# right_revision3_0.net
KiCad netlist of a schematic drawn in EAGLE
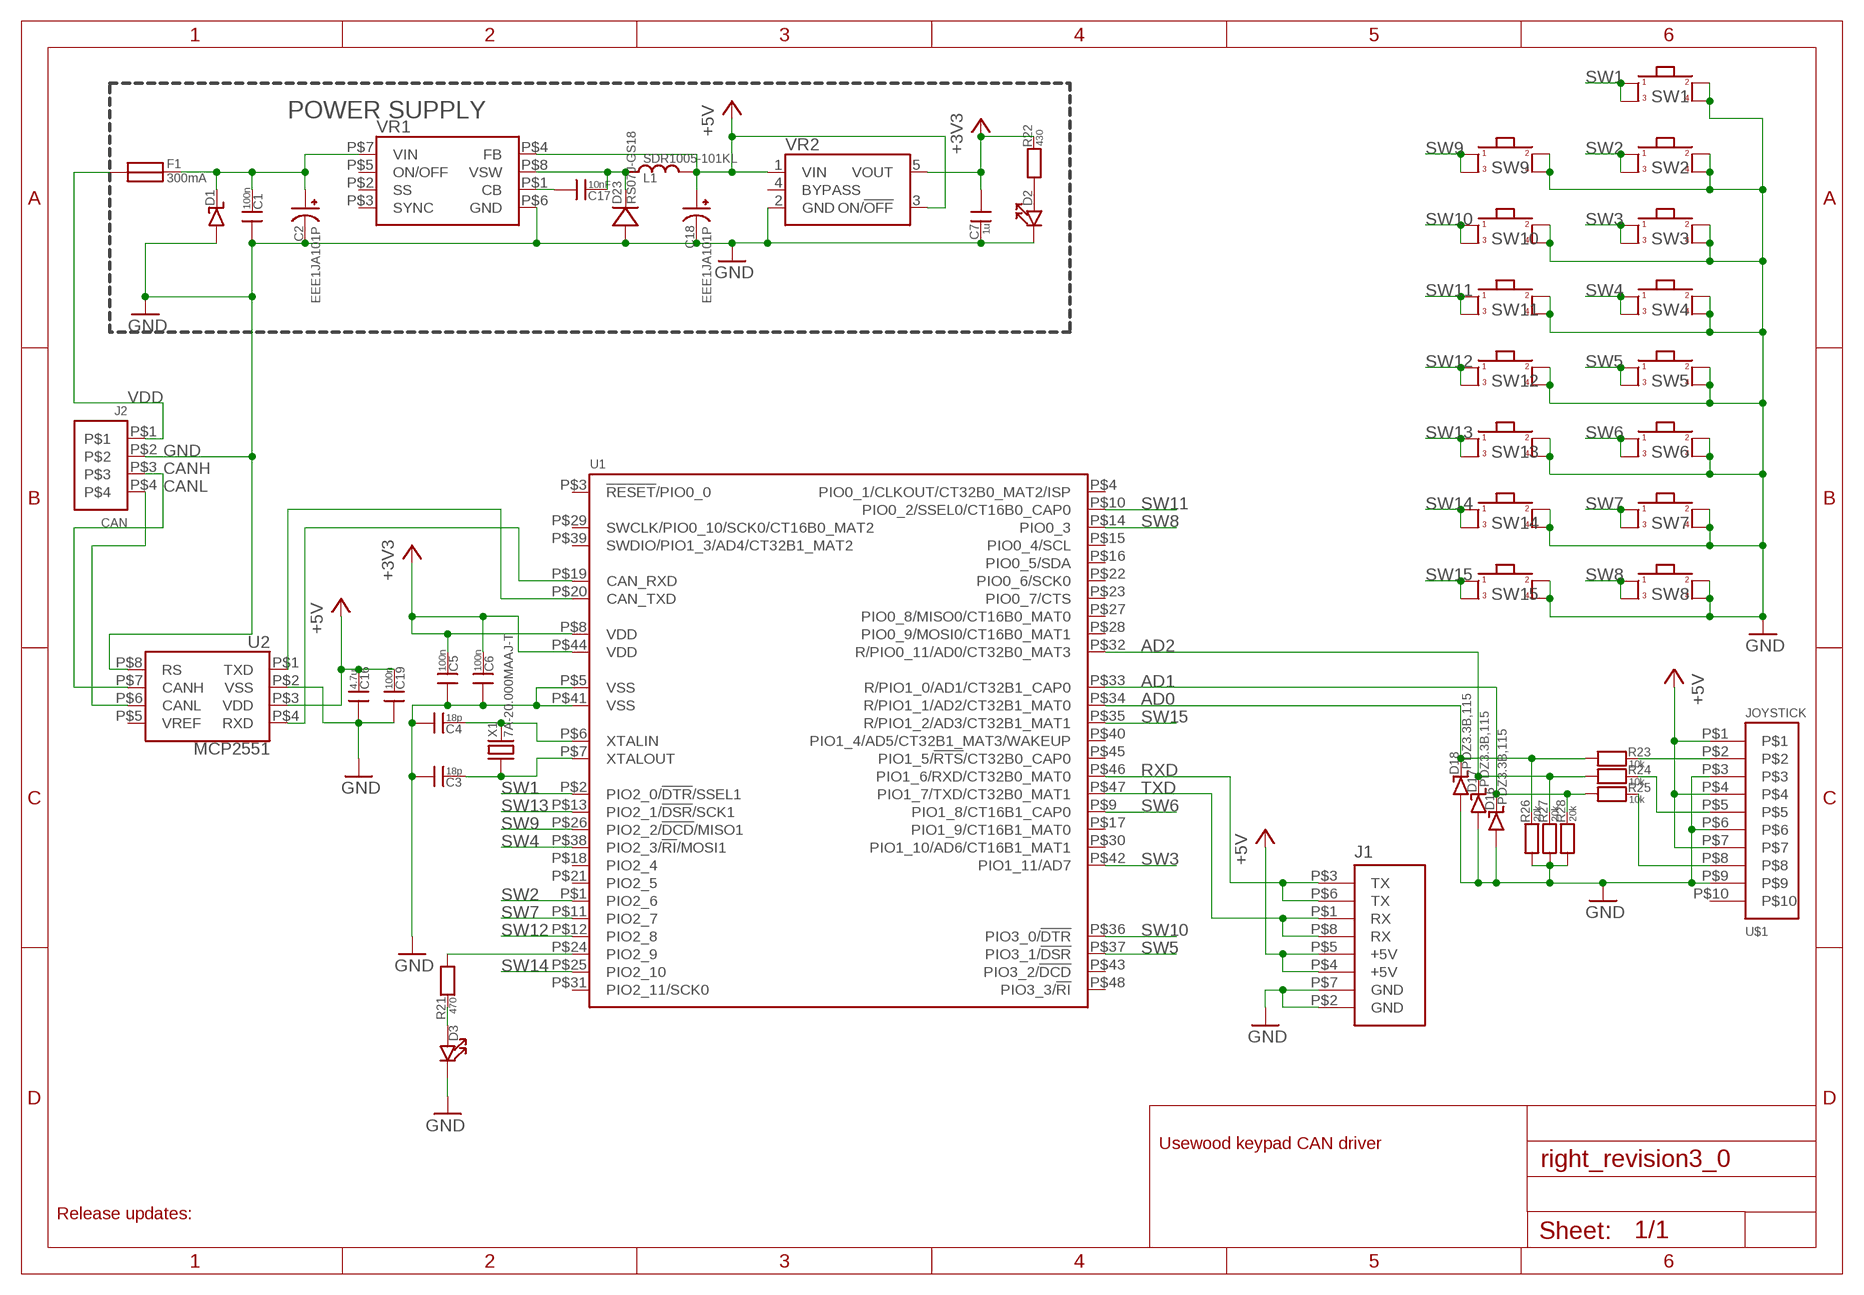
[diagram p0: schematic, sheet 1]

(export (version "E")
  (design (tool "Eeschema 10.0.6"))
  (components
    (comp (ref "C1")
      (value "100n")
      (footprint "eagle-import:0603_SILKSCREEN")
      (libsource (lib "eagle-import") (part "CAP_0603"))
    )
    (comp (ref "C2")
      (value "EEE1JA101P")
      (footprint "eagle-import:CAP_POL_SMD_10X10X10MM")
      (libsource (lib "eagle-import") (part "CAP_POLSMD_10X10X10MM"))
    )
    (comp (ref "C3")
      (value "18p")
      (footprint "eagle-import:0603_SILKSCREEN")
      (libsource (lib "eagle-import") (part "CAP_0603"))
    )
    (comp (ref "C4")
      (value "18p")
      (footprint "eagle-import:0603_SILKSCREEN")
      (libsource (lib "eagle-import") (part "CAP_0603"))
    )
    (comp (ref "C5")
      (value "100n")
      (footprint "eagle-import:0603_SILKSCREEN")
      (libsource (lib "eagle-import") (part "CAP_0603"))
    )
    (comp (ref "C6")
      (value "100n")
      (footprint "eagle-import:0603_SILKSCREEN")
      (libsource (lib "eagle-import") (part "CAP_0603"))
    )
    (comp (ref "C7")
      (value "1u")
      (footprint "eagle-import:0603_SILKSCREEN")
      (libsource (lib "eagle-import") (part "CAP_0603"))
    )
    (comp (ref "C16")
      (value "4.7u")
      (footprint "eagle-import:0603_SILKSCREEN")
      (libsource (lib "eagle-import") (part "CAP_0603"))
    )
    (comp (ref "C17")
      (value "10nF")
      (footprint "eagle-import:0603_SILKSCREEN")
      (libsource (lib "eagle-import") (part "CAP_0603"))
    )
    (comp (ref "C18")
      (value "EEE1JA101P")
      (footprint "eagle-import:CAP_POL_SMD_10X10X10MM")
      (libsource (lib "eagle-import") (part "CAP_POLSMD_10X10X10MM"))
    )
    (comp (ref "C19")
      (value "100n")
      (footprint "eagle-import:0603_SILKSCREEN")
      (libsource (lib "eagle-import") (part "CAP_0603"))
    )
    (comp (ref "D1")
      (value "DIODE_TVS_SMBJ33A-TRDO-214AA")
      (footprint "eagle-import:DO-214AA")
      (libsource (lib "eagle-import") (part "DIODE_TVS_SMBJ33A-TRDO-214AA"))
    )
    (comp (ref "D2")
      (value "LED_0603")
      (footprint "eagle-import:0603_SILKSCREEN")
      (libsource (lib "eagle-import") (part "LED_0603"))
    )
    (comp (ref "D3")
      (value "LED_0603")
      (footprint "eagle-import:0603_SILKSCREEN")
      (libsource (lib "eagle-import") (part "LED_0603"))
    )
    (comp (ref "D16")
      (value "PDZ3.3B,115")
      (footprint "eagle-import:SOD123")
      (libsource (lib "eagle-import") (part "DIODE_ZENERSDO123"))
    )
    (comp (ref "D17")
      (value "PDZ3.3B,115")
      (footprint "eagle-import:SOD123")
      (libsource (lib "eagle-import") (part "DIODE_ZENERSDO123"))
    )
    (comp (ref "D18")
      (value "PDZ3.3B,115")
      (footprint "eagle-import:SOD123")
      (libsource (lib "eagle-import") (part "DIODE_ZENERSDO123"))
    )
    (comp (ref "D23")
      (value "RS07J-GS18")
      (footprint "eagle-import:DO219AB")
      (libsource (lib "eagle-import") (part "DIODEDO219AB"))
    )
    (comp (ref "F1")
      (value "300mA")
      (footprint "eagle-import:FUSE_100MA")
      (libsource (lib "eagle-import") (part "FUSE_MC36204_100MA"))
    )
    (comp (ref "J1")
      (value "HEADER_USART_2_SMD")
      (footprint "eagle-import:HEADER_4_2_SMD")
      (libsource (lib "eagle-import") (part "HEADER_USART_2_SMD"))
    )
    (comp (ref "J2")
      (value "CAN")
      (footprint "eagle-import:MOLEX_MICRO_FIT_4WAY_SMD")
      (libsource (lib "eagle-import") (part "MOLEX_MICRO-FIT_4WAY_SMD"))
    )
    (comp (ref "L1")
      (value "SDR1005-101KL")
      (footprint "eagle-import:INDUCTOR_BOURNS_10X13X5MM")
      (libsource (lib "eagle-import") (part "INDUCTORBOURNS_10X13X5MM"))
    )
    (comp (ref "R21")
      (value "470")
      (footprint "eagle-import:0603_SILKSCREEN")
      (libsource (lib "eagle-import") (part "RES_0603"))
    )
    (comp (ref "R22")
      (value "430")
      (footprint "eagle-import:0603_SILKSCREEN")
      (libsource (lib "eagle-import") (part "RES_0603"))
    )
    (comp (ref "R23")
      (value "10k")
      (footprint "eagle-import:0603_SILKSCREEN")
      (libsource (lib "eagle-import") (part "RES_0603"))
    )
    (comp (ref "R24")
      (value "10k")
      (footprint "eagle-import:0603_SILKSCREEN")
      (libsource (lib "eagle-import") (part "RES_0603"))
    )
    (comp (ref "R25")
      (value "10k")
      (footprint "eagle-import:0603_SILKSCREEN")
      (libsource (lib "eagle-import") (part "RES_0603"))
    )
    (comp (ref "R26")
      (value "20k")
      (footprint "eagle-import:0603_SILKSCREEN")
      (libsource (lib "eagle-import") (part "RES_0603"))
    )
    (comp (ref "R27")
      (value "20k")
      (footprint "eagle-import:0603_SILKSCREEN")
      (libsource (lib "eagle-import") (part "RES_0603"))
    )
    (comp (ref "R28")
      (value "20k")
      (footprint "eagle-import:0603_SILKSCREEN")
      (libsource (lib "eagle-import") (part "RES_0603"))
    )
    (comp (ref "SW1")
      (value "SWITCH_EVQP6L")
      (footprint "eagle-import:SWITCH_EVQ9P6B40")
      (libsource (lib "eagle-import") (part "SWITCH_EVQP6L"))
    )
    (comp (ref "SW2")
      (value "SWITCH_EVQP6L")
      (footprint "eagle-import:SWITCH_EVQ9P6B40")
      (libsource (lib "eagle-import") (part "SWITCH_EVQP6L"))
    )
    (comp (ref "SW3")
      (value "SWITCH_EVQP6L")
      (footprint "eagle-import:SWITCH_EVQ9P6B40")
      (libsource (lib "eagle-import") (part "SWITCH_EVQP6L"))
    )
    (comp (ref "SW4")
      (value "SWITCH_EVQP6L")
      (footprint "eagle-import:SWITCH_EVQ9P6B40")
      (libsource (lib "eagle-import") (part "SWITCH_EVQP6L"))
    )
    (comp (ref "SW5")
      (value "SWITCH_EVQP6L")
      (footprint "eagle-import:SWITCH_EVQ9P6B40")
      (libsource (lib "eagle-import") (part "SWITCH_EVQP6L"))
    )
    (comp (ref "SW6")
      (value "SWITCH_EVQP6L")
      (footprint "eagle-import:SWITCH_EVQ9P6B40")
      (libsource (lib "eagle-import") (part "SWITCH_EVQP6L"))
    )
    (comp (ref "SW7")
      (value "SWITCH_EVQP6L")
      (footprint "eagle-import:SWITCH_EVQ9P6B40")
      (libsource (lib "eagle-import") (part "SWITCH_EVQP6L"))
    )
    (comp (ref "SW8")
      (value "SWITCH_EVQP6L")
      (footprint "eagle-import:SWITCH_EVQ9P6B40")
      (libsource (lib "eagle-import") (part "SWITCH_EVQP6L"))
    )
    (comp (ref "SW9")
      (value "SWITCH_EVQP6L")
      (footprint "eagle-import:SWITCH_EVQ9P6B40")
      (libsource (lib "eagle-import") (part "SWITCH_EVQP6L"))
    )
    (comp (ref "SW10")
      (value "SWITCH_EVQP6L")
      (footprint "eagle-import:SWITCH_EVQ9P6B40")
      (libsource (lib "eagle-import") (part "SWITCH_EVQP6L"))
    )
    (comp (ref "SW11")
      (value "SWITCH_EVQP6L")
      (footprint "eagle-import:SWITCH_EVQ9P6B40")
      (libsource (lib "eagle-import") (part "SWITCH_EVQP6L"))
    )
    (comp (ref "SW12")
      (value "SWITCH_EVQP6L")
      (footprint "eagle-import:SWITCH_EVQ9P6B40")
      (libsource (lib "eagle-import") (part "SWITCH_EVQP6L"))
    )
    (comp (ref "SW13")
      (value "SWITCH_EVQP6L")
      (footprint "eagle-import:SWITCH_EVQ9P6B40")
      (libsource (lib "eagle-import") (part "SWITCH_EVQP6L"))
    )
    (comp (ref "SW14")
      (value "SWITCH_EVQP6L")
      (footprint "eagle-import:SWITCH_EVQ9P6B40")
      (libsource (lib "eagle-import") (part "SWITCH_EVQP6L"))
    )
    (comp (ref "SW15")
      (value "SWITCH_EVQP6L")
      (footprint "eagle-import:SWITCH_EVQ9P6B40")
      (libsource (lib "eagle-import") (part "SWITCH_EVQP6L"))
    )
    (comp (ref "U$1")
      (value "JOYSTICK")
      (footprint "eagle-import:MOLEX_MICRO_FIT_10WAY_SMD")
      (libsource (lib "eagle-import") (part "MOLEX_MICRO-FIT_10WAY_SMD"))
    )
    (comp (ref "U1")
      (value "LPC11C14_QFP48")
      (footprint "eagle-import:QFP48")
      (libsource (lib "eagle-import") (part "LPC11C14_QFP48"))
    )
    (comp (ref "U2")
      (value "MCP2551")
      (footprint "eagle-import:SOIC8")
      (libsource (lib "eagle-import") (part "MCP2551_SOIC8"))
    )
    (comp (ref "VR1")
      (value "LM2671SOIC8")
      (footprint "eagle-import:SOIC8")
      (libsource (lib "eagle-import") (part "LM2671SOIC8"))
    )
    (comp (ref "VR2")
      (value "REG_LP2985_SOP5")
      (footprint "eagle-import:SOP5")
      (libsource (lib "eagle-import") (part "REG_LP2985_SOP5"))
    )
    (comp (ref "X1")
      (value "7A-20.000MAAJ-T")
      (footprint "eagle-import:XTAL_SMD_5X3.2")
      (libsource (lib "eagle-import") (part "XTAL_7A-12.000MAAJ-T"))
    )
  )
  (nets
    (net (code "1") (name "+3V3") (class "Default")
      (node (ref "C5") (pin "1") (pinfunction "P$2_1") (pintype "bidirectional"))
      (node (ref "C6") (pin "1") (pinfunction "P$2_1") (pintype "bidirectional"))
      (node (ref "C7") (pin "0") (pinfunction "P$1_0") (pintype "bidirectional"))
      (node (ref "R22") (pin "1") (pinfunction "P$2_1") (pintype "bidirectional"))
      (node (ref "U1") (pin "P$44") (pinfunction "VDD_P$44") (pintype "bidirectional"))
      (node (ref "U1") (pin "P$8") (pinfunction "VDD_P$8") (pintype "bidirectional"))
      (node (ref "VR2") (pin "5") (pinfunction "VOUT_5") (pintype "bidirectional"))
    )
    (net (code "2") (name "+5V") (class "Default")
      (node (ref "C16") (pin "1") (pinfunction "P$2_1") (pintype "bidirectional"))
      (node (ref "C18") (pin "+") (pinfunction "+_+") (pintype "bidirectional"))
      (node (ref "C19") (pin "1") (pinfunction "P$2_1") (pintype "bidirectional"))
      (node (ref "J1") (pin "P$4") (pinfunction "+5V_P$4") (pintype "bidirectional"))
      (node (ref "J1") (pin "P$5") (pinfunction "+5V_P$5") (pintype "bidirectional"))
      (node (ref "L1") (pin "P$2") (pinfunction "P$2_P$2") (pintype "bidirectional"))
      (node (ref "U$1") (pin "P$1") (pinfunction "P$1_P$1") (pintype "bidirectional"))
      (node (ref "U$1") (pin "P$4") (pinfunction "P$4_P$4") (pintype "bidirectional"))
      (node (ref "U$1") (pin "P$7") (pinfunction "P$7_P$7") (pintype "bidirectional"))
      (node (ref "U2") (pin "P$3") (pinfunction "VDD_P$3") (pintype "bidirectional"))
      (node (ref "VR1") (pin "P$4") (pinfunction "FB_P$4") (pintype "bidirectional"))
      (node (ref "VR2") (pin "1") (pinfunction "VIN_1") (pintype "bidirectional"))
      (node (ref "VR2") (pin "3") (pinfunction "ON/~{OFF}_3") (pintype "bidirectional"))
    )
    (net (code "3") (name "/AD0") (class "Default")
      (node (ref "D18") (pin "P$2") (pinfunction "N_P$2") (pintype "bidirectional"))
      (node (ref "R23") (pin "0") (pinfunction "P$1_0") (pintype "bidirectional"))
      (node (ref "R26") (pin "1") (pinfunction "P$2_1") (pintype "bidirectional"))
      (node (ref "U1") (pin "P$34") (pinfunction "R/PIO1_1/AD2/CT32B1_MAT0_P$34") (pintype "bidirectional"))
    )
    (net (code "4") (name "/AD1") (class "Default")
      (node (ref "D16") (pin "P$2") (pinfunction "N_P$2") (pintype "bidirectional"))
      (node (ref "R25") (pin "0") (pinfunction "P$1_0") (pintype "bidirectional"))
      (node (ref "R28") (pin "1") (pinfunction "P$2_1") (pintype "bidirectional"))
      (node (ref "U1") (pin "P$33") (pinfunction "R/PIO1_0/AD1/CT32B1_CAP0_P$33") (pintype "bidirectional"))
    )
    (net (code "5") (name "/AD2") (class "Default")
      (node (ref "D17") (pin "P$2") (pinfunction "N_P$2") (pintype "bidirectional"))
      (node (ref "R24") (pin "0") (pinfunction "P$1_0") (pintype "bidirectional"))
      (node (ref "R27") (pin "1") (pinfunction "P$2_1") (pintype "bidirectional"))
      (node (ref "U1") (pin "P$32") (pinfunction "R/PIO0_11/AD0/CT32B0_MAT3_P$32") (pintype "bidirectional"))
    )
    (net (code "6") (name "/CANH") (class "Default")
      (node (ref "J2") (pin "P$3") (pinfunction "P$3_P$3") (pintype "bidirectional"))
      (node (ref "U2") (pin "P$7") (pinfunction "CANH_P$7") (pintype "bidirectional"))
    )
    (net (code "7") (name "/CANL") (class "Default")
      (node (ref "J2") (pin "P$4") (pinfunction "P$4_P$4") (pintype "bidirectional"))
      (node (ref "U2") (pin "P$6") (pinfunction "CANL_P$6") (pintype "bidirectional"))
    )
    (net (code "8") (name "/RXD") (class "Default")
      (node (ref "J1") (pin "P$3") (pinfunction "TX_P$3") (pintype "bidirectional"))
      (node (ref "J1") (pin "P$6") (pinfunction "TX_P$6") (pintype "bidirectional"))
      (node (ref "U1") (pin "P$46") (pinfunction "PIO1_6/RXD/CT32B0_MAT0_P$46") (pintype "bidirectional"))
    )
    (net (code "9") (name "/SW1") (class "Default")
      (node (ref "SW1") (pin "A") (pinfunction "P$1_A") (pintype "bidirectional"))
      (node (ref "SW1") (pin "A'") (pinfunction "P$3_A'") (pintype "bidirectional"))
      (node (ref "U1") (pin "P$2") (pinfunction "PIO2_0/~{DTR}/SSEL1_P$2") (pintype "bidirectional"))
    )
    (net (code "10") (name "/SW2") (class "Default")
      (node (ref "SW2") (pin "A") (pinfunction "P$1_A") (pintype "bidirectional"))
      (node (ref "SW2") (pin "A'") (pinfunction "P$3_A'") (pintype "bidirectional"))
      (node (ref "U1") (pin "P$1") (pinfunction "PIO2_6_P$1") (pintype "bidirectional"))
    )
    (net (code "11") (name "/SW3") (class "Default")
      (node (ref "SW3") (pin "A") (pinfunction "P$1_A") (pintype "bidirectional"))
      (node (ref "SW3") (pin "A'") (pinfunction "P$3_A'") (pintype "bidirectional"))
      (node (ref "U1") (pin "P$42") (pinfunction "PIO1_11/AD7_P$42") (pintype "bidirectional"))
    )
    (net (code "12") (name "/SW4") (class "Default")
      (node (ref "SW4") (pin "A") (pinfunction "P$1_A") (pintype "bidirectional"))
      (node (ref "SW4") (pin "A'") (pinfunction "P$3_A'") (pintype "bidirectional"))
      (node (ref "U1") (pin "P$38") (pinfunction "PIO2_3/~{RI}/MOSI1_P$38") (pintype "bidirectional"))
    )
    (net (code "13") (name "/SW5") (class "Default")
      (node (ref "SW5") (pin "A") (pinfunction "P$1_A") (pintype "bidirectional"))
      (node (ref "SW5") (pin "A'") (pinfunction "P$3_A'") (pintype "bidirectional"))
      (node (ref "U1") (pin "P$37") (pinfunction "PIO3_1/~{DSR}_P$37") (pintype "bidirectional"))
    )
    (net (code "14") (name "/SW6") (class "Default")
      (node (ref "SW6") (pin "A") (pinfunction "P$1_A") (pintype "bidirectional"))
      (node (ref "SW6") (pin "A'") (pinfunction "P$3_A'") (pintype "bidirectional"))
      (node (ref "U1") (pin "P$9") (pinfunction "PIO1_8/CT16B1_CAP0_P$9") (pintype "bidirectional"))
    )
    (net (code "15") (name "/SW7") (class "Default")
      (node (ref "SW7") (pin "A") (pinfunction "P$1_A") (pintype "bidirectional"))
      (node (ref "SW7") (pin "A'") (pinfunction "P$3_A'") (pintype "bidirectional"))
      (node (ref "U1") (pin "P$11") (pinfunction "PIO2_7_P$11") (pintype "bidirectional"))
    )
    (net (code "16") (name "/SW8") (class "Default")
      (node (ref "SW8") (pin "A") (pinfunction "P$1_A") (pintype "bidirectional"))
      (node (ref "SW8") (pin "A'") (pinfunction "P$3_A'") (pintype "bidirectional"))
      (node (ref "U1") (pin "P$14") (pinfunction "PIO0_3_P$14") (pintype "bidirectional"))
    )
    (net (code "17") (name "/SW9") (class "Default")
      (node (ref "SW9") (pin "A") (pinfunction "P$1_A") (pintype "bidirectional"))
      (node (ref "SW9") (pin "A'") (pinfunction "P$3_A'") (pintype "bidirectional"))
      (node (ref "U1") (pin "P$26") (pinfunction "PIO2_2/~{DCD}/MISO1_P$26") (pintype "bidirectional"))
    )
    (net (code "18") (name "/SW10") (class "Default")
      (node (ref "SW10") (pin "A") (pinfunction "P$1_A") (pintype "bidirectional"))
      (node (ref "SW10") (pin "A'") (pinfunction "P$3_A'") (pintype "bidirectional"))
      (node (ref "U1") (pin "P$36") (pinfunction "PIO3_0/~{DTR}_P$36") (pintype "bidirectional"))
    )
    (net (code "19") (name "/SW11") (class "Default")
      (node (ref "SW11") (pin "A") (pinfunction "P$1_A") (pintype "bidirectional"))
      (node (ref "SW11") (pin "A'") (pinfunction "P$3_A'") (pintype "bidirectional"))
      (node (ref "U1") (pin "P$10") (pinfunction "PIO0_2/SSEL0/CT16B0_CAP0_P$10") (pintype "bidirectional"))
    )
    (net (code "20") (name "/SW12") (class "Default")
      (node (ref "SW12") (pin "A") (pinfunction "P$1_A") (pintype "bidirectional"))
      (node (ref "SW12") (pin "A'") (pinfunction "P$3_A'") (pintype "bidirectional"))
      (node (ref "U1") (pin "P$12") (pinfunction "PIO2_8_P$12") (pintype "bidirectional"))
    )
    (net (code "21") (name "/SW13") (class "Default")
      (node (ref "SW13") (pin "A") (pinfunction "P$1_A") (pintype "bidirectional"))
      (node (ref "SW13") (pin "A'") (pinfunction "P$3_A'") (pintype "bidirectional"))
      (node (ref "U1") (pin "P$13") (pinfunction "PIO2_1/~{DSR}/SCK1_P$13") (pintype "bidirectional"))
    )
    (net (code "22") (name "/SW14") (class "Default")
      (node (ref "SW14") (pin "A") (pinfunction "P$1_A") (pintype "bidirectional"))
      (node (ref "SW14") (pin "A'") (pinfunction "P$3_A'") (pintype "bidirectional"))
      (node (ref "U1") (pin "P$25") (pinfunction "PIO2_10_P$25") (pintype "bidirectional"))
    )
    (net (code "23") (name "/SW15") (class "Default")
      (node (ref "SW15") (pin "A") (pinfunction "P$1_A") (pintype "bidirectional"))
      (node (ref "SW15") (pin "A'") (pinfunction "P$3_A'") (pintype "bidirectional"))
      (node (ref "U1") (pin "P$35") (pinfunction "R/PIO1_2/AD3/CT32B1_MAT1_P$35") (pintype "bidirectional"))
    )
    (net (code "24") (name "/TXD") (class "Default")
      (node (ref "J1") (pin "P$1") (pinfunction "RX_P$1") (pintype "bidirectional"))
      (node (ref "J1") (pin "P$8") (pinfunction "RX_P$8") (pintype "bidirectional"))
      (node (ref "U1") (pin "P$47") (pinfunction "PIO1_7/TXD/CT32B0_MAT1_P$47") (pintype "bidirectional"))
    )
    (net (code "25") (name "/VDD") (class "Default")
      (node (ref "F1") (pin "P$1") (pinfunction "P$1_P$1") (pintype "bidirectional"))
      (node (ref "J2") (pin "P$1") (pinfunction "P$1_P$1") (pintype "bidirectional"))
    )
    (net (code "26") (name "GND") (class "Default")
      (node (ref "C1") (pin "0") (pinfunction "P$1_0") (pintype "bidirectional"))
      (node (ref "C16") (pin "0") (pinfunction "P$1_0") (pintype "bidirectional"))
      (node (ref "C18") (pin "-") (pinfunction "-_-") (pintype "bidirectional"))
      (node (ref "C19") (pin "0") (pinfunction "P$1_0") (pintype "bidirectional"))
      (node (ref "C2") (pin "-") (pinfunction "-_-") (pintype "bidirectional"))
      (node (ref "C3") (pin "0") (pinfunction "P$1_0") (pintype "bidirectional"))
      (node (ref "C4") (pin "0") (pinfunction "P$1_0") (pintype "bidirectional"))
      (node (ref "C5") (pin "0") (pinfunction "P$1_0") (pintype "bidirectional"))
      (node (ref "C6") (pin "0") (pinfunction "P$1_0") (pintype "bidirectional"))
      (node (ref "C7") (pin "1") (pinfunction "P$2_1") (pintype "bidirectional"))
      (node (ref "D1") (pin "P$1") (pinfunction "P_P$1") (pintype "bidirectional"))
      (node (ref "D16") (pin "P$1") (pinfunction "P_P$1") (pintype "bidirectional"))
      (node (ref "D17") (pin "P$1") (pinfunction "P_P$1") (pintype "bidirectional"))
      (node (ref "D18") (pin "P$1") (pinfunction "P_P$1") (pintype "bidirectional"))
      (node (ref "D2") (pin "1") (pinfunction "1_1") (pintype "bidirectional"))
      (node (ref "D23") (pin "P$1") (pinfunction "P_P$1") (pintype "bidirectional"))
      (node (ref "D3") (pin "1") (pinfunction "1_1") (pintype "bidirectional"))
      (node (ref "J1") (pin "P$2") (pinfunction "GND_P$2") (pintype "bidirectional"))
      (node (ref "J1") (pin "P$7") (pinfunction "GND_P$7") (pintype "bidirectional"))
      (node (ref "J2") (pin "P$2") (pinfunction "P$2_P$2") (pintype "bidirectional"))
      (node (ref "R26") (pin "0") (pinfunction "P$1_0") (pintype "bidirectional"))
      (node (ref "R27") (pin "0") (pinfunction "P$1_0") (pintype "bidirectional"))
      (node (ref "R28") (pin "0") (pinfunction "P$1_0") (pintype "bidirectional"))
      (node (ref "SW1") (pin "B") (pinfunction "P$2_B") (pintype "bidirectional"))
      (node (ref "SW1") (pin "B'") (pinfunction "P$4_B'") (pintype "bidirectional"))
      (node (ref "SW10") (pin "B") (pinfunction "P$2_B") (pintype "bidirectional"))
      (node (ref "SW10") (pin "B'") (pinfunction "P$4_B'") (pintype "bidirectional"))
      (node (ref "SW11") (pin "B") (pinfunction "P$2_B") (pintype "bidirectional"))
      (node (ref "SW11") (pin "B'") (pinfunction "P$4_B'") (pintype "bidirectional"))
      (node (ref "SW12") (pin "B") (pinfunction "P$2_B") (pintype "bidirectional"))
      (node (ref "SW12") (pin "B'") (pinfunction "P$4_B'") (pintype "bidirectional"))
      (node (ref "SW13") (pin "B") (pinfunction "P$2_B") (pintype "bidirectional"))
      (node (ref "SW13") (pin "B'") (pinfunction "P$4_B'") (pintype "bidirectional"))
      (node (ref "SW14") (pin "B") (pinfunction "P$2_B") (pintype "bidirectional"))
      (node (ref "SW14") (pin "B'") (pinfunction "P$4_B'") (pintype "bidirectional"))
      (node (ref "SW15") (pin "B") (pinfunction "P$2_B") (pintype "bidirectional"))
      (node (ref "SW15") (pin "B'") (pinfunction "P$4_B'") (pintype "bidirectional"))
      (node (ref "SW2") (pin "B") (pinfunction "P$2_B") (pintype "bidirectional"))
      (node (ref "SW2") (pin "B'") (pinfunction "P$4_B'") (pintype "bidirectional"))
      (node (ref "SW3") (pin "B") (pinfunction "P$2_B") (pintype "bidirectional"))
      (node (ref "SW3") (pin "B'") (pinfunction "P$4_B'") (pintype "bidirectional"))
      (node (ref "SW4") (pin "B") (pinfunction "P$2_B") (pintype "bidirectional"))
      (node (ref "SW4") (pin "B'") (pinfunction "P$4_B'") (pintype "bidirectional"))
      (node (ref "SW5") (pin "B") (pinfunction "P$2_B") (pintype "bidirectional"))
      (node (ref "SW5") (pin "B'") (pinfunction "P$4_B'") (pintype "bidirectional"))
      (node (ref "SW6") (pin "B") (pinfunction "P$2_B") (pintype "bidirectional"))
      (node (ref "SW6") (pin "B'") (pinfunction "P$4_B'") (pintype "bidirectional"))
      (node (ref "SW7") (pin "B") (pinfunction "P$2_B") (pintype "bidirectional"))
      (node (ref "SW7") (pin "B'") (pinfunction "P$4_B'") (pintype "bidirectional"))
      (node (ref "SW8") (pin "B") (pinfunction "P$2_B") (pintype "bidirectional"))
      (node (ref "SW8") (pin "B'") (pinfunction "P$4_B'") (pintype "bidirectional"))
      (node (ref "SW9") (pin "B") (pinfunction "P$2_B") (pintype "bidirectional"))
      (node (ref "SW9") (pin "B'") (pinfunction "P$4_B'") (pintype "bidirectional"))
      (node (ref "U$1") (pin "P$3") (pinfunction "P$3_P$3") (pintype "bidirectional"))
      (node (ref "U$1") (pin "P$6") (pinfunction "P$6_P$6") (pintype "bidirectional"))
      (node (ref "U$1") (pin "P$9") (pinfunction "P$9_P$9") (pintype "bidirectional"))
      (node (ref "U1") (pin "P$41") (pinfunction "VSS_P$41") (pintype "bidirectional"))
      (node (ref "U1") (pin "P$5") (pinfunction "VSS_P$5") (pintype "bidirectional"))
      (node (ref "U2") (pin "P$2") (pinfunction "VSS_P$2") (pintype "bidirectional"))
      (node (ref "U2") (pin "P$8") (pinfunction "RS_P$8") (pintype "bidirectional"))
      (node (ref "VR1") (pin "P$6") (pinfunction "GND_P$6") (pintype "bidirectional"))
      (node (ref "VR2") (pin "2") (pinfunction "GND_2") (pintype "bidirectional"))
    )
    (net (code "27") (name "Net-(C1-P$2)") (class "Default")
      (node (ref "C1") (pin "1") (pinfunction "P$2_1") (pintype "bidirectional"))
      (node (ref "C2") (pin "+") (pinfunction "+_+") (pintype "bidirectional"))
      (node (ref "D1") (pin "P$2") (pinfunction "N_P$2") (pintype "bidirectional"))
      (node (ref "F1") (pin "P$2") (pinfunction "P$2_P$2") (pintype "bidirectional"))
      (node (ref "VR1") (pin "P$7") (pinfunction "VIN_P$7") (pintype "bidirectional"))
    )
    (net (code "28") (name "Net-(C3-P$2)") (class "Default")
      (node (ref "C3") (pin "1") (pinfunction "P$2_1") (pintype "bidirectional"))
      (node (ref "U1") (pin "P$7") (pinfunction "XTALOUT_P$7") (pintype "bidirectional"))
      (node (ref "X1") (pin "P$1") (pinfunction "P$1_P$1") (pintype "bidirectional"))
    )
    (net (code "29") (name "Net-(C4-P$2)") (class "Default")
      (node (ref "C4") (pin "1") (pinfunction "P$2_1") (pintype "bidirectional"))
      (node (ref "U1") (pin "P$6") (pinfunction "XTALIN_P$6") (pintype "bidirectional"))
      (node (ref "X1") (pin "P$2") (pinfunction "P$2_P$2") (pintype "bidirectional"))
    )
    (net (code "30") (name "Net-(C17-P$1)") (class "Default")
      (node (ref "C17") (pin "0") (pinfunction "P$1_0") (pintype "bidirectional"))
      (node (ref "VR1") (pin "P$1") (pinfunction "CB_P$1") (pintype "bidirectional"))
    )
    (net (code "31") (name "Net-(C17-P$2)") (class "Default")
      (node (ref "C17") (pin "1") (pinfunction "P$2_1") (pintype "bidirectional"))
      (node (ref "D23") (pin "P$2") (pinfunction "N_P$2") (pintype "bidirectional"))
      (node (ref "L1") (pin "P$1") (pinfunction "P$1_P$1") (pintype "bidirectional"))
      (node (ref "VR1") (pin "P$8") (pinfunction "VSW_P$8") (pintype "bidirectional"))
    )
    (net (code "32") (name "Net-(R21-P$1)") (class "Default")
      (node (ref "R21") (pin "0") (pinfunction "P$1_0") (pintype "bidirectional"))
      (node (ref "U1") (pin "P$24") (pinfunction "PIO2_9_P$24") (pintype "bidirectional"))
    )
    (net (code "33") (name "Net-(R21-P$2)") (class "Default")
      (node (ref "D3") (pin "0") (pinfunction "0_0") (pintype "bidirectional"))
      (node (ref "R21") (pin "1") (pinfunction "P$2_1") (pintype "bidirectional"))
    )
    (net (code "34") (name "Net-(R22-P$1)") (class "Default")
      (node (ref "D2") (pin "0") (pinfunction "0_0") (pintype "bidirectional"))
      (node (ref "R22") (pin "0") (pinfunction "P$1_0") (pintype "bidirectional"))
    )
    (net (code "35") (name "Net-(R23-P$2)") (class "Default")
      (node (ref "R23") (pin "1") (pinfunction "P$2_1") (pintype "bidirectional"))
      (node (ref "U$1") (pin "P$2") (pinfunction "P$2_P$2") (pintype "bidirectional"))
    )
    (net (code "36") (name "Net-(R24-P$2)") (class "Default")
      (node (ref "R24") (pin "1") (pinfunction "P$2_1") (pintype "bidirectional"))
      (node (ref "U$1") (pin "P$5") (pinfunction "P$5_P$5") (pintype "bidirectional"))
    )
    (net (code "37") (name "Net-(R25-P$2)") (class "Default")
      (node (ref "R25") (pin "1") (pinfunction "P$2_1") (pintype "bidirectional"))
      (node (ref "U$1") (pin "P$8") (pinfunction "P$8_P$8") (pintype "bidirectional"))
    )
    (net (code "38") (name "Net-(U1-CAN_RXD)") (class "Default")
      (node (ref "U1") (pin "P$19") (pinfunction "CAN_RXD_P$19") (pintype "bidirectional"))
      (node (ref "U2") (pin "P$4") (pinfunction "RXD_P$4") (pintype "bidirectional"))
    )
    (net (code "39") (name "Net-(U1-CAN_TXD)") (class "Default")
      (node (ref "U1") (pin "P$20") (pinfunction "CAN_TXD_P$20") (pintype "bidirectional"))
      (node (ref "U2") (pin "P$1") (pinfunction "TXD_P$1") (pintype "bidirectional"))
    )
    (net (code "40") (name "unconnected-(U$1-PadP$10)") (class "Default")
      (node (ref "U$1") (pin "P$10") (pinfunction "P$10_P$10") (pintype "bidirectional"))
    )
    (net (code "41") (name "unconnected-(U1-PIO0_1{slash}CLKOUT{slash}CT32B0_MAT2{slash}ISP-PadP$4)") (class "Default")
      (node (ref "U1") (pin "P$4") (pinfunction "PIO0_1/CLKOUT/CT32B0_MAT2/ISP_P$4") (pintype "bidirectional"))
    )
    (net (code "42") (name "unconnected-(U1-PIO0_4{slash}SCL-PadP$15)") (class "Default")
      (node (ref "U1") (pin "P$15") (pinfunction "PIO0_4/SCL_P$15") (pintype "bidirectional"))
    )
    (net (code "43") (name "unconnected-(U1-PIO0_5{slash}SDA-PadP$16)") (class "Default")
      (node (ref "U1") (pin "P$16") (pinfunction "PIO0_5/SDA_P$16") (pintype "bidirectional"))
    )
    (net (code "44") (name "unconnected-(U1-PIO0_6{slash}SCK0-PadP$22)") (class "Default")
      (node (ref "U1") (pin "P$22") (pinfunction "PIO0_6/SCK0_P$22") (pintype "bidirectional"))
    )
    (net (code "45") (name "unconnected-(U1-PIO0_7{slash}CTS-PadP$23)") (class "Default")
      (node (ref "U1") (pin "P$23") (pinfunction "PIO0_7/CTS_P$23") (pintype "bidirectional"))
    )
    (net (code "46") (name "unconnected-(U1-PIO0_8{slash}MISO0{slash}CT16B0_MAT0-PadP$27)") (class "Default")
      (node (ref "U1") (pin "P$27") (pinfunction "PIO0_8/MISO0/CT16B0_MAT0_P$27") (pintype "bidirectional"))
    )
    (net (code "47") (name "unconnected-(U1-PIO0_9{slash}MOSI0{slash}CT16B0_MAT1-PadP$28)") (class "Default")
      (node (ref "U1") (pin "P$28") (pinfunction "PIO0_9/MOSI0/CT16B0_MAT1_P$28") (pintype "bidirectional"))
    )
    (net (code "48") (name "unconnected-(U1-PIO1_4{slash}AD5{slash}CT32B1_MAT3{slash}WAKEUP-PadP$40)") (class "Default")
      (node (ref "U1") (pin "P$40") (pinfunction "PIO1_4/AD5/CT32B1_MAT3/WAKEUP_P$40") (pintype "bidirectional"))
    )
    (net (code "49") (name "unconnected-(U1-PIO1_5{slash}~{RTS}{slash}CT32B0_CAP0-PadP$45)") (class "Default")
      (node (ref "U1") (pin "P$45") (pinfunction "PIO1_5/~{RTS}/CT32B0_CAP0_P$45") (pintype "bidirectional"))
    )
    (net (code "50") (name "unconnected-(U1-PIO1_9{slash}CT16B1_MAT0-PadP$17)") (class "Default")
      (node (ref "U1") (pin "P$17") (pinfunction "PIO1_9/CT16B1_MAT0_P$17") (pintype "bidirectional"))
    )
    (net (code "51") (name "unconnected-(U1-PIO1_10{slash}AD6{slash}CT16B1_MAT1-PadP$30)") (class "Default")
      (node (ref "U1") (pin "P$30") (pinfunction "PIO1_10/AD6/CT16B1_MAT1_P$30") (pintype "bidirectional"))
    )
    (net (code "52") (name "unconnected-(U1-PIO2_4-PadP$18)") (class "Default")
      (node (ref "U1") (pin "P$18") (pinfunction "PIO2_4_P$18") (pintype "bidirectional"))
    )
    (net (code "53") (name "unconnected-(U1-PIO2_5-PadP$21)") (class "Default")
      (node (ref "U1") (pin "P$21") (pinfunction "PIO2_5_P$21") (pintype "bidirectional"))
    )
    (net (code "54") (name "unconnected-(U1-PIO2_11{slash}SCK0-PadP$31)") (class "Default")
      (node (ref "U1") (pin "P$31") (pinfunction "PIO2_11/SCK0_P$31") (pintype "bidirectional"))
    )
    (net (code "55") (name "unconnected-(U1-PIO3_2{slash}~{DCD}-PadP$43)") (class "Default")
      (node (ref "U1") (pin "P$43") (pinfunction "PIO3_2/~{DCD}_P$43") (pintype "bidirectional"))
    )
    (net (code "56") (name "unconnected-(U1-PIO3_3{slash}~{RI}-PadP$48)") (class "Default")
      (node (ref "U1") (pin "P$48") (pinfunction "PIO3_3/~{RI}_P$48") (pintype "bidirectional"))
    )
    (net (code "57") (name "unconnected-(U1-SWCLK{slash}PIO0_10{slash}SCK0{slash}CT16B0_MAT2-PadP$29)") (class "Default")
      (node (ref "U1") (pin "P$29") (pinfunction "SWCLK/PIO0_10/SCK0/CT16B0_MAT2_P$29") (pintype "bidirectional"))
    )
    (net (code "58") (name "unconnected-(U1-SWDIO{slash}PIO1_3{slash}AD4{slash}CT32B1_MAT2-PadP$39)") (class "Default")
      (node (ref "U1") (pin "P$39") (pinfunction "SWDIO/PIO1_3/AD4/CT32B1_MAT2_P$39") (pintype "bidirectional"))
    )
    (net (code "59") (name "unconnected-(U1-~{RESET}{slash}PIO0_0-PadP$3)") (class "Default")
      (node (ref "U1") (pin "P$3") (pinfunction "~{RESET}/PIO0_0_P$3") (pintype "bidirectional"))
    )
    (net (code "60") (name "unconnected-(U2-VREF-PadP$5)") (class "Default")
      (node (ref "U2") (pin "P$5") (pinfunction "VREF_P$5") (pintype "bidirectional"))
    )
    (net (code "61") (name "unconnected-(VR1-ON{slash}OFF-PadP$5)") (class "Default")
      (node (ref "VR1") (pin "P$5") (pinfunction "ON/OFF_P$5") (pintype "bidirectional"))
    )
    (net (code "62") (name "unconnected-(VR1-SS-PadP$2)") (class "Default")
      (node (ref "VR1") (pin "P$2") (pinfunction "SS_P$2") (pintype "bidirectional"))
    )
    (net (code "63") (name "unconnected-(VR1-SYNC-PadP$3)") (class "Default")
      (node (ref "VR1") (pin "P$3") (pinfunction "SYNC_P$3") (pintype "bidirectional"))
    )
    (net (code "64") (name "unconnected-(VR2-BYPASS-Pad4)") (class "Default")
      (node (ref "VR2") (pin "4") (pinfunction "BYPASS_4") (pintype "bidirectional"))
    )
  )
)
